# ProPrj_Smart_security_2024-12-20.net
KiCad netlist of a schematic drawn in EasyEDA Pro
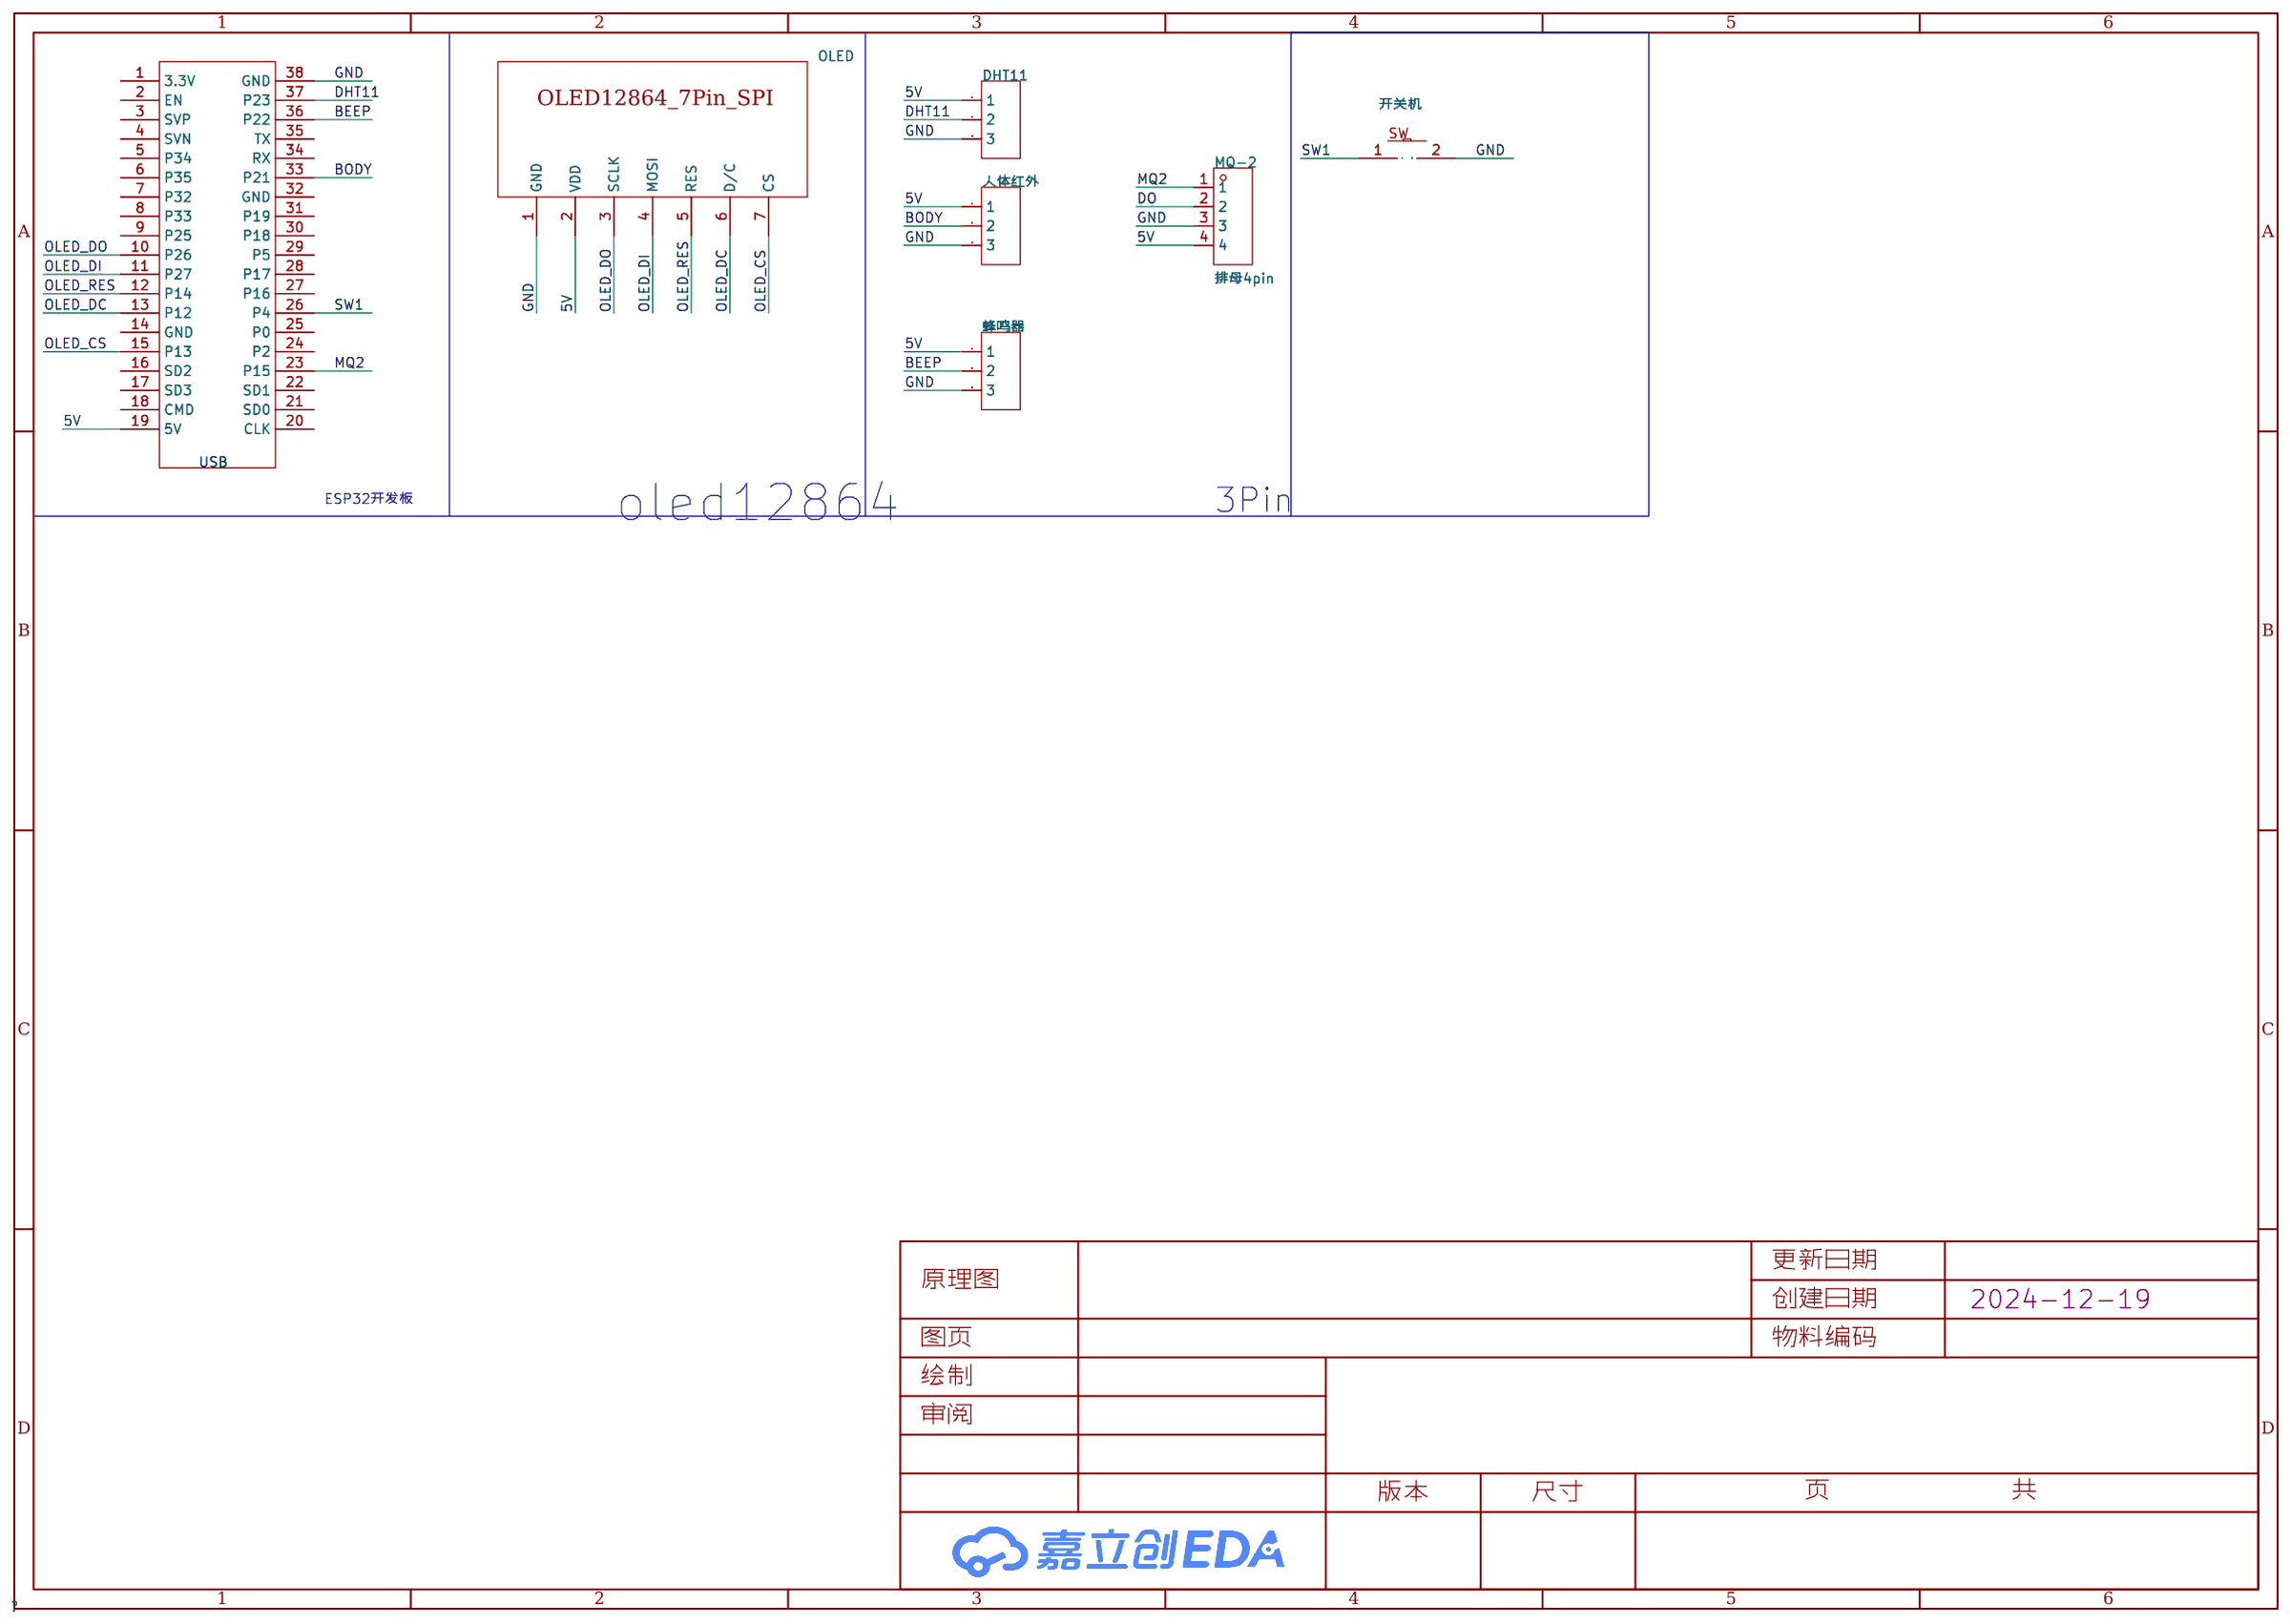
[diagram p0: schematic sheet]

(export (version "E")
  (design (tool "Eeschema 10.0.6"))
  (components
    (comp (ref "DHT11")
      (value "DHT11")
      (footprint "easyedapro:HDR-F-2.54_1X3")
      (libsource (lib "easyedapro") (part "排母3PIN"))
    )
    (comp (ref "ESP32_38PIN_1")
      (value "~")
      (footprint "easyedapro:ESP32_38PIN教学")
      (libsource (lib "easyedapro") (part "ESP32_38PIN"))
    )
    (comp (ref "MQ-2")
      (value "排母4pin")
      (footprint "easyedapro:排母4PIN")
      (libsource (lib "easyedapro") (part "排母4pin"))
    )
    (comp (ref "OLED")
      (value "OLED12864_7Pin_SPI")
      (footprint "easyedapro:OLED-12864(7PIN-SPI)")
      (libsource (lib "easyedapro") (part "OLED12864_7Pin_SPI"))
    )
    (comp (ref "人体红外")
      (value "人体红外")
      (footprint "easyedapro:HDR-F-2.54_1X3")
      (libsource (lib "easyedapro") (part "排母3PIN"))
    )
    (comp (ref "开关机") (value "~") (footprint "easyedapro:pb") (libsource (lib "easyedapro") (part "按键")))
    (comp (ref "蜂鸣器")
      (value "蜂鸣器")
      (footprint "easyedapro:HDR-F-2.54_1X3")
      (libsource (lib "easyedapro") (part "排母3PIN"))
    )
  )
  (nets
    (net (code "1") (name "/5V") (class "Default")
      (node (ref "DHT11") (pin "1") (pinfunction "1_1") (pintype "input"))
      (node (ref "ESP32_38PIN_1") (pin "19") (pinfunction "5V_19") (pintype "input"))
      (node (ref "MQ-2") (pin "4") (pinfunction "4_4") (pintype "unspecified"))
      (node (ref "OLED") (pin "2") (pinfunction "VDD_2") (pintype "input"))
      (node (ref "人体红外") (pin "1") (pinfunction "1_1") (pintype "input"))
      (node (ref "蜂鸣器") (pin "1") (pinfunction "1_1") (pintype "input"))
    )
    (net (code "2") (name "/BEEP") (class "Default")
      (node (ref "ESP32_38PIN_1") (pin "36") (pinfunction "P22_36") (pintype "input"))
      (node (ref "蜂鸣器") (pin "2") (pinfunction "2_2") (pintype "input"))
    )
    (net (code "3") (name "/BODY") (class "Default")
      (node (ref "ESP32_38PIN_1") (pin "33") (pinfunction "P21_33") (pintype "input"))
      (node (ref "人体红外") (pin "2") (pinfunction "2_2") (pintype "input"))
    )
    (net (code "4") (name "/DHT11") (class "Default")
      (node (ref "DHT11") (pin "2") (pinfunction "2_2") (pintype "input"))
      (node (ref "ESP32_38PIN_1") (pin "37") (pinfunction "P23_37") (pintype "input"))
    )
    (net (code "5") (name "/DO") (class "Default")
      (node (ref "MQ-2") (pin "2") (pinfunction "2_2") (pintype "unspecified"))
    )
    (net (code "6") (name "/GND") (class "Default")
      (node (ref "DHT11") (pin "3") (pinfunction "3_3") (pintype "input"))
      (node (ref "ESP32_38PIN_1") (pin "38") (pinfunction "GND_38") (pintype "input"))
      (node (ref "MQ-2") (pin "3") (pinfunction "3_3") (pintype "unspecified"))
      (node (ref "OLED") (pin "1") (pinfunction "GND_1") (pintype "input"))
      (node (ref "人体红外") (pin "3") (pinfunction "3_3") (pintype "input"))
      (node (ref "开关机") (pin "2") (pinfunction "2_2") (pintype "input"))
      (node (ref "蜂鸣器") (pin "3") (pinfunction "3_3") (pintype "input"))
    )
    (net (code "7") (name "/MQ2") (class "Default")
      (node (ref "ESP32_38PIN_1") (pin "23") (pinfunction "P15_23") (pintype "input"))
      (node (ref "MQ-2") (pin "1") (pinfunction "1_1") (pintype "unspecified"))
    )
    (net (code "8") (name "/OLED_CS") (class "Default")
      (node (ref "ESP32_38PIN_1") (pin "15") (pinfunction "P13_15") (pintype "input"))
      (node (ref "OLED") (pin "7") (pinfunction "CS_7") (pintype "input"))
    )
    (net (code "9") (name "/OLED_DC") (class "Default")
      (node (ref "ESP32_38PIN_1") (pin "13") (pinfunction "P12_13") (pintype "input"))
      (node (ref "OLED") (pin "6") (pinfunction "D/C_6") (pintype "input"))
    )
    (net (code "10") (name "/OLED_DI") (class "Default")
      (node (ref "ESP32_38PIN_1") (pin "11") (pinfunction "P27_11") (pintype "input"))
      (node (ref "OLED") (pin "4") (pinfunction "MOSI_4") (pintype "input"))
    )
    (net (code "11") (name "/OLED_DO") (class "Default")
      (node (ref "ESP32_38PIN_1") (pin "10") (pinfunction "P26_10") (pintype "input"))
      (node (ref "OLED") (pin "3") (pinfunction "SCLK_3") (pintype "input"))
    )
    (net (code "12") (name "/OLED_RES") (class "Default")
      (node (ref "ESP32_38PIN_1") (pin "12") (pinfunction "P14_12") (pintype "input"))
      (node (ref "OLED") (pin "5") (pinfunction "RES_5") (pintype "input"))
    )
    (net (code "13") (name "/SW1") (class "Default")
      (node (ref "ESP32_38PIN_1") (pin "26") (pinfunction "P4_26") (pintype "input"))
      (node (ref "开关机") (pin "1") (pinfunction "1_1") (pintype "input"))
    )
    (net (code "14") (name "unconnected-(ESP32_38PIN_1-3.3V-Pad1)") (class "Default")
      (node (ref "ESP32_38PIN_1") (pin "1") (pinfunction "3.3V_1") (pintype "input"))
    )
    (net (code "15") (name "unconnected-(ESP32_38PIN_1-CLK-Pad20)") (class "Default")
      (node (ref "ESP32_38PIN_1") (pin "20") (pinfunction "CLK_20") (pintype "input"))
    )
    (net (code "16") (name "unconnected-(ESP32_38PIN_1-CMD-Pad18)") (class "Default")
      (node (ref "ESP32_38PIN_1") (pin "18") (pinfunction "CMD_18") (pintype "input"))
    )
    (net (code "17") (name "unconnected-(ESP32_38PIN_1-EN-Pad2)") (class "Default")
      (node (ref "ESP32_38PIN_1") (pin "2") (pinfunction "EN_2") (pintype "input"))
    )
    (net (code "18") (name "unconnected-(ESP32_38PIN_1-GND-Pad14)") (class "Default")
      (node (ref "ESP32_38PIN_1") (pin "14") (pinfunction "GND_14") (pintype "input"))
    )
    (net (code "19") (name "unconnected-(ESP32_38PIN_1-GND-Pad32)") (class "Default")
      (node (ref "ESP32_38PIN_1") (pin "32") (pinfunction "GND_32") (pintype "input"))
    )
    (net (code "20") (name "unconnected-(ESP32_38PIN_1-P0-Pad25)") (class "Default")
      (node (ref "ESP32_38PIN_1") (pin "25") (pinfunction "P0_25") (pintype "input"))
    )
    (net (code "21") (name "unconnected-(ESP32_38PIN_1-P2-Pad24)") (class "Default")
      (node (ref "ESP32_38PIN_1") (pin "24") (pinfunction "P2_24") (pintype "input"))
    )
    (net (code "22") (name "unconnected-(ESP32_38PIN_1-P5-Pad29)") (class "Default")
      (node (ref "ESP32_38PIN_1") (pin "29") (pinfunction "P5_29") (pintype "input"))
    )
    (net (code "23") (name "unconnected-(ESP32_38PIN_1-P16-Pad27)") (class "Default")
      (node (ref "ESP32_38PIN_1") (pin "27") (pinfunction "P16_27") (pintype "input"))
    )
    (net (code "24") (name "unconnected-(ESP32_38PIN_1-P17-Pad28)") (class "Default")
      (node (ref "ESP32_38PIN_1") (pin "28") (pinfunction "P17_28") (pintype "input"))
    )
    (net (code "25") (name "unconnected-(ESP32_38PIN_1-P18-Pad30)") (class "Default")
      (node (ref "ESP32_38PIN_1") (pin "30") (pinfunction "P18_30") (pintype "input"))
    )
    (net (code "26") (name "unconnected-(ESP32_38PIN_1-P19-Pad31)") (class "Default")
      (node (ref "ESP32_38PIN_1") (pin "31") (pinfunction "P19_31") (pintype "input"))
    )
    (net (code "27") (name "unconnected-(ESP32_38PIN_1-P25-Pad9)") (class "Default")
      (node (ref "ESP32_38PIN_1") (pin "9") (pinfunction "P25_9") (pintype "input"))
    )
    (net (code "28") (name "unconnected-(ESP32_38PIN_1-P32-Pad7)") (class "Default")
      (node (ref "ESP32_38PIN_1") (pin "7") (pinfunction "P32_7") (pintype "input"))
    )
    (net (code "29") (name "unconnected-(ESP32_38PIN_1-P33-Pad8)") (class "Default")
      (node (ref "ESP32_38PIN_1") (pin "8") (pinfunction "P33_8") (pintype "input"))
    )
    (net (code "30") (name "unconnected-(ESP32_38PIN_1-P34-Pad5)") (class "Default")
      (node (ref "ESP32_38PIN_1") (pin "5") (pinfunction "P34_5") (pintype "input"))
    )
    (net (code "31") (name "unconnected-(ESP32_38PIN_1-P35-Pad6)") (class "Default")
      (node (ref "ESP32_38PIN_1") (pin "6") (pinfunction "P35_6") (pintype "input"))
    )
    (net (code "32") (name "unconnected-(ESP32_38PIN_1-RX-Pad34)") (class "Default")
      (node (ref "ESP32_38PIN_1") (pin "34") (pinfunction "RX_34") (pintype "input"))
    )
    (net (code "33") (name "unconnected-(ESP32_38PIN_1-SD0-Pad21)") (class "Default")
      (node (ref "ESP32_38PIN_1") (pin "21") (pinfunction "SD0_21") (pintype "input"))
    )
    (net (code "34") (name "unconnected-(ESP32_38PIN_1-SD1-Pad22)") (class "Default")
      (node (ref "ESP32_38PIN_1") (pin "22") (pinfunction "SD1_22") (pintype "input"))
    )
    (net (code "35") (name "unconnected-(ESP32_38PIN_1-SD2-Pad16)") (class "Default")
      (node (ref "ESP32_38PIN_1") (pin "16") (pinfunction "SD2_16") (pintype "input"))
    )
    (net (code "36") (name "unconnected-(ESP32_38PIN_1-SD3-Pad17)") (class "Default")
      (node (ref "ESP32_38PIN_1") (pin "17") (pinfunction "SD3_17") (pintype "input"))
    )
    (net (code "37") (name "unconnected-(ESP32_38PIN_1-SVN-Pad4)") (class "Default")
      (node (ref "ESP32_38PIN_1") (pin "4") (pinfunction "SVN_4") (pintype "input"))
    )
    (net (code "38") (name "unconnected-(ESP32_38PIN_1-SVP-Pad3)") (class "Default")
      (node (ref "ESP32_38PIN_1") (pin "3") (pinfunction "SVP_3") (pintype "input"))
    )
    (net (code "39") (name "unconnected-(ESP32_38PIN_1-TX-Pad35)") (class "Default")
      (node (ref "ESP32_38PIN_1") (pin "35") (pinfunction "TX_35") (pintype "input"))
    )
  )
)
